# receiver.net
KiCad netlist of a schematic drawn in EAGLE
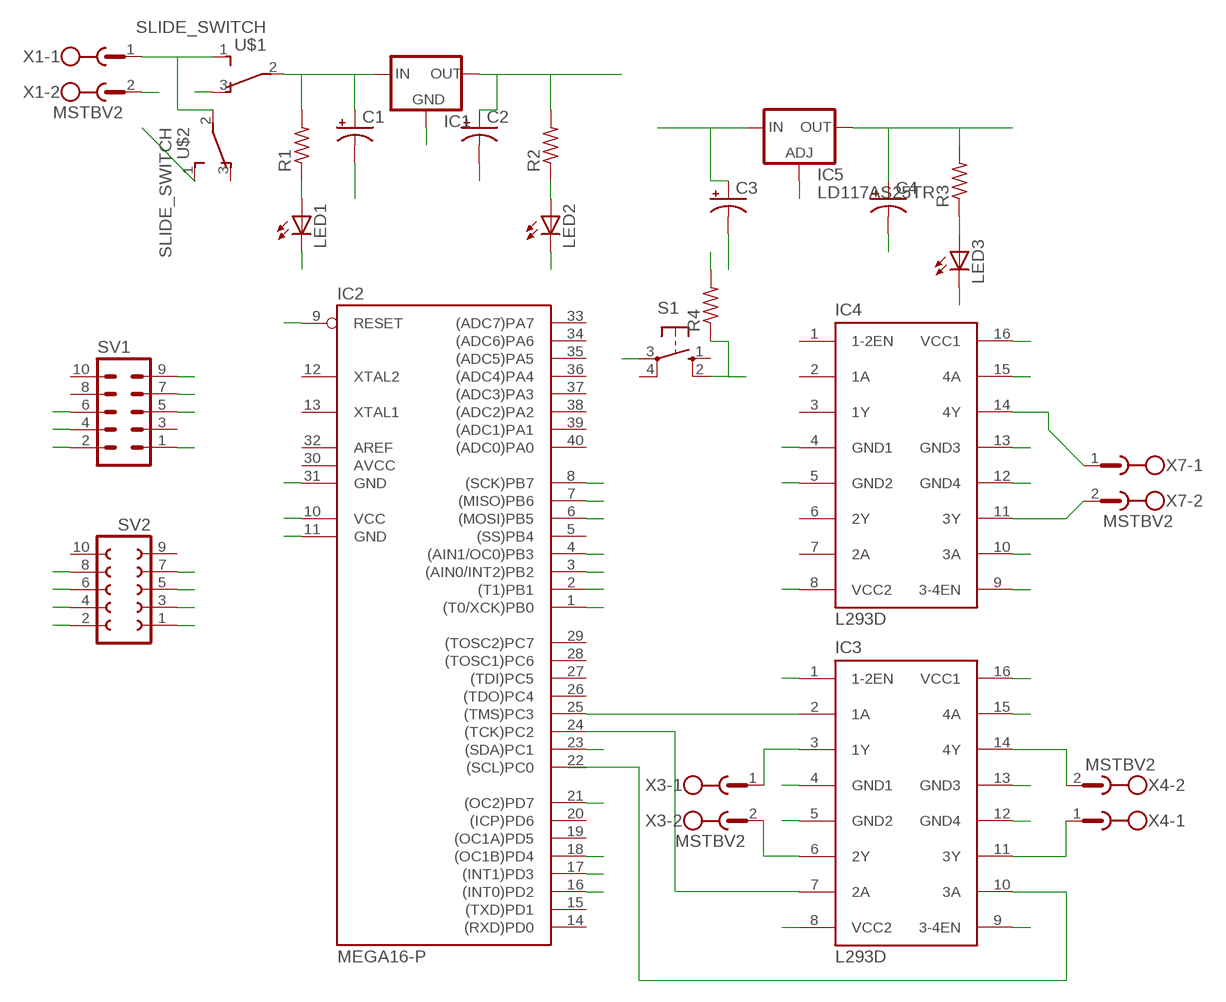
[diagram p0: schematic, sheet 1]

(export (version "E")
  (design (tool "Eeschema 10.0.6"))
  (components
    (comp (ref "C1")
      (value "CPOL-USE2.5-6")
      (footprint "eagle-import:E2,5-6")
      (libsource (lib "eagle-import") (part "CPOL-USE2.5-6"))
    )
    (comp (ref "C2")
      (value "CPOL-USE2.5-6")
      (footprint "eagle-import:E2,5-6")
      (libsource (lib "eagle-import") (part "CPOL-USE2.5-6"))
    )
    (comp (ref "C3")
      (value "CPOL-USE2.5-6")
      (footprint "eagle-import:E2,5-6")
      (libsource (lib "eagle-import") (part "CPOL-USE2.5-6"))
    )
    (comp (ref "C4")
      (value "CPOL-USE2.5-6")
      (footprint "eagle-import:E2,5-6")
      (libsource (lib "eagle-import") (part "CPOL-USE2.5-6"))
    )
    (comp (ref "IC1")
      (value "78XXS")
      (footprint "eagle-import:78XXS")
      (libsource (lib "eagle-import") (part "78XXS"))
    )
    (comp (ref "IC2")
      (value "MEGA16-P")
      (footprint "eagle-import:DIL40")
      (fields (field (name "MPN") "ATMEGA16-16PU"))
      (libsource (lib "eagle-import") (part "MEGA16-P"))
    )
    (comp (ref "IC3")
      (value "L293D")
      (footprint "eagle-import:DIL16")
      (libsource (lib "eagle-import") (part "L293D"))
    )
    (comp (ref "IC4")
      (value "L293D")
      (footprint "eagle-import:DIL16")
      (libsource (lib "eagle-import") (part "L293D"))
    )
    (comp (ref "IC5")
      (value "LD117AS25TR")
      (footprint "eagle-import:SOT223")
      (libsource (lib "eagle-import") (part "LD117A?S25TR"))
    )
    (comp (ref "LED1")
      (value "LED3MM")
      (footprint "eagle-import:LED3MM")
      (libsource (lib "eagle-import") (part "LED3MM"))
    )
    (comp (ref "LED2")
      (value "LED3MM")
      (footprint "eagle-import:LED3MM")
      (libsource (lib "eagle-import") (part "LED3MM"))
    )
    (comp (ref "LED3")
      (value "LED3MM")
      (footprint "eagle-import:LED3MM")
      (libsource (lib "eagle-import") (part "LED3MM"))
    )
    (comp (ref "R1")
      (value "R-US_0207/10")
      (footprint "eagle-import:0207_10")
      (libsource (lib "eagle-import") (part "R-US_0207/10"))
    )
    (comp (ref "R2")
      (value "R-US_0207/10")
      (footprint "eagle-import:0207_10")
      (libsource (lib "eagle-import") (part "R-US_0207/10"))
    )
    (comp (ref "R3")
      (value "R-US_0207/10")
      (footprint "eagle-import:0207_10")
      (libsource (lib "eagle-import") (part "R-US_0207/10"))
    )
    (comp (ref "R4")
      (value "R-US_0207/10")
      (footprint "eagle-import:0207_10")
      (libsource (lib "eagle-import") (part "R-US_0207/10"))
    )
    (comp (ref "S1")
      (value "10-XX")
      (footprint "eagle-import:B3F-10XX")
      (fields (field (name "MPN") "B3F-1000"))
      (libsource (lib "eagle-import") (part "10-XX"))
    )
    (comp (ref "SV1")
      (value "ML10")
      (footprint "eagle-import:ML10")
      (libsource (lib "eagle-import") (part "ML10"))
    )
    (comp (ref "SV2")
      (value "FE05-2")
      (footprint "eagle-import:FE05-2")
      (libsource (lib "eagle-import") (part "FE05-2"))
    )
    (comp (ref "U$1")
      (value "SLIDE_SWITCH")
      (footprint "eagle-import:SPDT")
      (libsource (lib "eagle-import") (part "SLIDE_SWITCH"))
    )
    (comp (ref "U$2")
      (value "SLIDE_SWITCH")
      (footprint "eagle-import:SPDT")
      (libsource (lib "eagle-import") (part "SLIDE_SWITCH"))
    )
    (comp (ref "X1")
      (value "MSTBV2")
      (footprint "eagle-import:MSTBV2")
      (fields (field (name "MPN") "MSTBV 2,5/2-GF-5.08"))
      (libsource (lib "eagle-import") (part "MSTBV2"))
    )
    (comp (ref "X3")
      (value "MSTBV2")
      (footprint "eagle-import:MSTBV2")
      (fields (field (name "MPN") "MSTBV 2,5/2-GF-5.08"))
      (libsource (lib "eagle-import") (part "MSTBV2"))
    )
    (comp (ref "X4")
      (value "MSTBV2")
      (footprint "eagle-import:MSTBV2")
      (fields (field (name "MPN") "MSTBV 2,5/2-GF-5.08"))
      (libsource (lib "eagle-import") (part "MSTBV2"))
    )
    (comp (ref "X7")
      (value "MSTBV2")
      (footprint "eagle-import:MSTBV2")
      (fields (field (name "MPN") "MSTBV 2,5/2-GF-5.08"))
      (libsource (lib "eagle-import") (part "MSTBV2"))
    )
  )
  (nets
    (net (code "1") (name "/16") (class "Default")
      (node (ref "IC2") (pin "16") (pinfunction "(INT0)PD2_16") (pintype "bidirectional"))
      (node (ref "IC4") (pin "15") (pinfunction "4A_15") (pintype "input"))
    )
    (net (code "2") (name "/17") (class "Default")
      (node (ref "IC2") (pin "17") (pinfunction "(INT1)PD3_17") (pintype "bidirectional"))
      (node (ref "IC4") (pin "10") (pinfunction "3A_10") (pintype "input"))
    )
    (net (code "3") (name "/23") (class "Default")
      (node (ref "IC2") (pin "23") (pinfunction "(SDA)PC1_23") (pintype "bidirectional"))
      (node (ref "IC3") (pin "15") (pinfunction "4A_15") (pintype "input"))
    )
    (net (code "4") (name "/AVCC") (class "Default")
      (node (ref "IC2") (pin "30") (pinfunction "AVCC_30") (pintype "power_in"))
    )
    (net (code "5") (name "/CE") (class "Default")
      (node (ref "IC2") (pin "1") (pinfunction "(T0/XCK)PB0_1") (pintype "bidirectional"))
      (node (ref "SV2") (pin "3") (pinfunction "3_3") (pintype "passive"))
    )
    (net (code "6") (name "/CSN") (class "Default")
      (node (ref "IC2") (pin "2") (pinfunction "(T1)PB1_2") (pintype "bidirectional"))
      (node (ref "SV2") (pin "4") (pinfunction "4_4") (pintype "passive"))
    )
    (net (code "7") (name "/EN12") (class "Default")
      (node (ref "IC2") (pin "4") (pinfunction "(AIN1/OC0)PB3_4") (pintype "bidirectional"))
      (node (ref "IC3") (pin "1") (pinfunction "1-2EN_1") (pintype "input"))
    )
    (net (code "8") (name "/EN34") (class "Default")
      (node (ref "IC2") (pin "21") (pinfunction "(OC2)PD7_21") (pintype "bidirectional"))
      (node (ref "IC3") (pin "9") (pinfunction "3-4EN_9") (pintype "input"))
    )
    (net (code "9") (name "/GND") (class "Default")
      (node (ref "C1") (pin "-") (pinfunction "-_-") (pintype "passive"))
      (node (ref "C2") (pin "-") (pinfunction "-_-") (pintype "passive"))
      (node (ref "C3") (pin "-") (pinfunction "-_-") (pintype "passive"))
      (node (ref "C4") (pin "-") (pinfunction "-_-") (pintype "passive"))
      (node (ref "IC1") (pin "GND") (pinfunction "GND_GND") (pintype "input"))
      (node (ref "IC2") (pin "11") (pinfunction "GND_11") (pintype "power_in"))
      (node (ref "IC2") (pin "31") (pinfunction "GND_31") (pintype "power_in"))
      (node (ref "IC3") (pin "12") (pinfunction "GND4_12") (pintype "power_in"))
      (node (ref "IC3") (pin "13") (pinfunction "GND3_13") (pintype "power_in"))
      (node (ref "IC3") (pin "4") (pinfunction "GND1_4") (pintype "power_in"))
      (node (ref "IC3") (pin "5") (pinfunction "GND2_5") (pintype "power_in"))
      (node (ref "IC4") (pin "12") (pinfunction "GND4_12") (pintype "power_in"))
      (node (ref "IC4") (pin "13") (pinfunction "GND3_13") (pintype "power_in"))
      (node (ref "IC4") (pin "4") (pinfunction "GND1_4") (pintype "power_in"))
      (node (ref "IC4") (pin "5") (pinfunction "GND2_5") (pintype "power_in"))
      (node (ref "IC5") (pin "1") (pinfunction "ADJ_1") (pintype "input"))
      (node (ref "LED1") (pin "K") (pinfunction "C_K") (pintype "passive"))
      (node (ref "LED2") (pin "K") (pinfunction "C_K") (pintype "passive"))
      (node (ref "LED3") (pin "K") (pinfunction "C_K") (pintype "passive"))
      (node (ref "S1") (pin "3") (pinfunction "P_3") (pintype "passive"))
      (node (ref "SV1") (pin "4") (pinfunction "4_4") (pintype "passive"))
      (node (ref "SV1") (pin "6") (pinfunction "6_6") (pintype "passive"))
      (node (ref "SV2") (pin "1") (pinfunction "1_1") (pintype "passive"))
      (node (ref "U$1") (pin "3") (pinfunction "NC_3") (pintype "passive"))
      (node (ref "X1") (pin "2") (pinfunction "1_2") (pintype "passive"))
    )
    (net (code "10") (name "/IRQ") (class "Default")
      (node (ref "IC2") (pin "3") (pinfunction "(AIN0/INT2)PB2_3") (pintype "bidirectional"))
      (node (ref "SV2") (pin "8") (pinfunction "8_8") (pintype "passive"))
    )
    (net (code "11") (name "/MISO") (class "Default")
      (node (ref "IC2") (pin "7") (pinfunction "(MISO)PB6_7") (pintype "bidirectional"))
      (node (ref "SV1") (pin "9") (pinfunction "9_9") (pintype "passive"))
      (node (ref "SV2") (pin "7") (pinfunction "7_7") (pintype "passive"))
    )
    (net (code "12") (name "/MOSI") (class "Default")
      (node (ref "IC2") (pin "6") (pinfunction "(MOSI)PB5_6") (pintype "bidirectional"))
      (node (ref "SV1") (pin "1") (pinfunction "1_1") (pintype "passive"))
      (node (ref "SV2") (pin "6") (pinfunction "6_6") (pintype "passive"))
    )
    (net (code "13") (name "/OC1B") (class "Default")
      (node (ref "IC2") (pin "18") (pinfunction "(OC1B)PD4_18") (pintype "bidirectional"))
      (node (ref "IC4") (pin "9") (pinfunction "3-4EN_9") (pintype "input"))
    )
    (net (code "14") (name "/RST") (class "Default")
      (node (ref "IC2") (pin "9") (pinfunction "RESET_9") (pintype "input"))
      (node (ref "R4") (pin "1") (pinfunction "1_1") (pintype "passive"))
      (node (ref "S1") (pin "2") (pinfunction "S1_2") (pintype "passive"))
      (node (ref "SV1") (pin "5") (pinfunction "5_5") (pintype "passive"))
    )
    (net (code "15") (name "/SCK") (class "Default")
      (node (ref "IC2") (pin "8") (pinfunction "(SCK)PB7_8") (pintype "bidirectional"))
      (node (ref "SV1") (pin "7") (pinfunction "7_7") (pintype "passive"))
      (node (ref "SV2") (pin "5") (pinfunction "5_5") (pintype "passive"))
    )
    (net (code "16") (name "/VCC") (class "Default")
      (node (ref "C2") (pin "+") (pinfunction "+_+") (pintype "passive"))
      (node (ref "C3") (pin "+") (pinfunction "+_+") (pintype "passive"))
      (node (ref "IC1") (pin "OUT") (pinfunction "OUT_OUT") (pintype "passive"))
      (node (ref "IC2") (pin "10") (pinfunction "VCC_10") (pintype "power_in"))
      (node (ref "IC3") (pin "16") (pinfunction "VCC1_16") (pintype "power_in"))
      (node (ref "IC4") (pin "16") (pinfunction "VCC1_16") (pintype "power_in"))
      (node (ref "IC5") (pin "3") (pinfunction "IN_3") (pintype "input"))
      (node (ref "R2") (pin "2") (pinfunction "2_2") (pintype "passive"))
      (node (ref "R4") (pin "2") (pinfunction "2_2") (pintype "passive"))
      (node (ref "SV1") (pin "2") (pinfunction "2_2") (pintype "passive"))
    )
    (net (code "17") (name "/VCC3.3") (class "Default")
      (node (ref "C4") (pin "+") (pinfunction "+_+") (pintype "passive"))
      (node (ref "IC5") (pin "4") (pinfunction "OUT_4") (pintype "passive"))
      (node (ref "R3") (pin "2") (pinfunction "2_2") (pintype "passive"))
      (node (ref "SV2") (pin "2") (pinfunction "2_2") (pintype "passive"))
    )
    (net (code "18") (name "/VCC12") (class "Default")
      (node (ref "IC3") (pin "8") (pinfunction "VCC2_8") (pintype "power_in"))
      (node (ref "IC4") (pin "8") (pinfunction "VCC2_8") (pintype "power_in"))
      (node (ref "U$2") (pin "1") (pinfunction "NO_1") (pintype "passive"))
    )
    (net (code "19") (name "Net-(IC2-(SCL)PC0)") (class "Default")
      (node (ref "IC2") (pin "22") (pinfunction "(SCL)PC0_22") (pintype "bidirectional"))
      (node (ref "IC3") (pin "10") (pinfunction "3A_10") (pintype "input"))
    )
    (net (code "20") (name "Net-(IC2-(TCK)PC2)") (class "Default")
      (node (ref "IC2") (pin "24") (pinfunction "(TCK)PC2_24") (pintype "bidirectional"))
      (node (ref "IC3") (pin "7") (pinfunction "2A_7") (pintype "input"))
    )
    (net (code "21") (name "Net-(IC2-(TMS)PC3)") (class "Default")
      (node (ref "IC2") (pin "25") (pinfunction "(TMS)PC3_25") (pintype "bidirectional"))
      (node (ref "IC3") (pin "2") (pinfunction "1A_2") (pintype "input"))
    )
    (net (code "22") (name "Net-(IC3-1Y)") (class "Default")
      (node (ref "IC3") (pin "3") (pinfunction "1Y_3") (pintype "output"))
      (node (ref "X3") (pin "1") (pinfunction "1_1") (pintype "passive"))
    )
    (net (code "23") (name "Net-(IC3-2Y)") (class "Default")
      (node (ref "IC3") (pin "6") (pinfunction "2Y_6") (pintype "output"))
      (node (ref "X3") (pin "2") (pinfunction "1_2") (pintype "passive"))
    )
    (net (code "24") (name "Net-(IC3-3Y)") (class "Default")
      (node (ref "IC3") (pin "11") (pinfunction "3Y_11") (pintype "output"))
      (node (ref "X4") (pin "1") (pinfunction "1_1") (pintype "passive"))
    )
    (net (code "25") (name "Net-(IC3-4Y)") (class "Default")
      (node (ref "IC3") (pin "14") (pinfunction "4Y_14") (pintype "output"))
      (node (ref "X4") (pin "2") (pinfunction "1_2") (pintype "passive"))
    )
    (net (code "26") (name "Net-(IC4-3Y)") (class "Default")
      (node (ref "IC4") (pin "11") (pinfunction "3Y_11") (pintype "output"))
      (node (ref "X7") (pin "2") (pinfunction "1_2") (pintype "passive"))
    )
    (net (code "27") (name "Net-(IC4-4Y)") (class "Default")
      (node (ref "IC4") (pin "14") (pinfunction "4Y_14") (pintype "output"))
      (node (ref "X7") (pin "1") (pinfunction "1_1") (pintype "passive"))
    )
    (net (code "28") (name "Net-(LED1-PadA)") (class "Default")
      (node (ref "LED1") (pin "A") (pinfunction "A_A") (pintype "passive"))
      (node (ref "R1") (pin "1") (pinfunction "1_1") (pintype "passive"))
    )
    (net (code "29") (name "Net-(LED2-PadA)") (class "Default")
      (node (ref "LED2") (pin "A") (pinfunction "A_A") (pintype "passive"))
      (node (ref "R2") (pin "1") (pinfunction "1_1") (pintype "passive"))
    )
    (net (code "30") (name "Net-(LED3-PadA)") (class "Default")
      (node (ref "LED3") (pin "A") (pinfunction "A_A") (pintype "passive"))
      (node (ref "R3") (pin "1") (pinfunction "1_1") (pintype "passive"))
    )
    (net (code "31") (name "Net-(U$1-NO)") (class "Default")
      (node (ref "U$1") (pin "1") (pinfunction "NO_1") (pintype "passive"))
      (node (ref "U$2") (pin "2") (pinfunction "P_2") (pintype "passive"))
      (node (ref "X1") (pin "1") (pinfunction "1_1") (pintype "passive"))
    )
    (net (code "32") (name "Net-(U$1-P)") (class "Default")
      (node (ref "C1") (pin "+") (pinfunction "+_+") (pintype "passive"))
      (node (ref "IC1") (pin "IN") (pinfunction "IN_IN") (pintype "input"))
      (node (ref "R1") (pin "2") (pinfunction "2_2") (pintype "passive"))
      (node (ref "U$1") (pin "2") (pinfunction "P_2") (pintype "passive"))
    )
    (net (code "33") (name "unconnected-(IC2-(ADC0)PA0-Pad40)") (class "Default")
      (node (ref "IC2") (pin "40") (pinfunction "(ADC0)PA0_40") (pintype "bidirectional"))
    )
    (net (code "34") (name "unconnected-(IC2-(ADC1)PA1-Pad39)") (class "Default")
      (node (ref "IC2") (pin "39") (pinfunction "(ADC1)PA1_39") (pintype "bidirectional"))
    )
    (net (code "35") (name "unconnected-(IC2-(ADC2)PA2-Pad38)") (class "Default")
      (node (ref "IC2") (pin "38") (pinfunction "(ADC2)PA2_38") (pintype "bidirectional"))
    )
    (net (code "36") (name "unconnected-(IC2-(ADC3)PA3-Pad37)") (class "Default")
      (node (ref "IC2") (pin "37") (pinfunction "(ADC3)PA3_37") (pintype "bidirectional"))
    )
    (net (code "37") (name "unconnected-(IC2-(ADC4)PA4-Pad36)") (class "Default")
      (node (ref "IC2") (pin "36") (pinfunction "(ADC4)PA4_36") (pintype "bidirectional"))
    )
    (net (code "38") (name "unconnected-(IC2-(ADC5)PA5-Pad35)") (class "Default")
      (node (ref "IC2") (pin "35") (pinfunction "(ADC5)PA5_35") (pintype "bidirectional"))
    )
    (net (code "39") (name "unconnected-(IC2-(ADC6)PA6-Pad34)") (class "Default")
      (node (ref "IC2") (pin "34") (pinfunction "(ADC6)PA6_34") (pintype "bidirectional"))
    )
    (net (code "40") (name "unconnected-(IC2-(ADC7)PA7-Pad33)") (class "Default")
      (node (ref "IC2") (pin "33") (pinfunction "(ADC7)PA7_33") (pintype "bidirectional"))
    )
    (net (code "41") (name "unconnected-(IC2-(ICP)PD6-Pad20)") (class "Default")
      (node (ref "IC2") (pin "20") (pinfunction "(ICP)PD6_20") (pintype "bidirectional"))
    )
    (net (code "42") (name "unconnected-(IC2-(OC1A)PD5-Pad19)") (class "Default")
      (node (ref "IC2") (pin "19") (pinfunction "(OC1A)PD5_19") (pintype "bidirectional"))
    )
    (net (code "43") (name "unconnected-(IC2-(RXD)PD0-Pad14)") (class "Default")
      (node (ref "IC2") (pin "14") (pinfunction "(RXD)PD0_14") (pintype "bidirectional"))
    )
    (net (code "44") (name "unconnected-(IC2-(SS)PB4-Pad5)") (class "Default")
      (node (ref "IC2") (pin "5") (pinfunction "(SS)PB4_5") (pintype "bidirectional"))
    )
    (net (code "45") (name "unconnected-(IC2-(TDI)PC5-Pad27)") (class "Default")
      (node (ref "IC2") (pin "27") (pinfunction "(TDI)PC5_27") (pintype "bidirectional"))
    )
    (net (code "46") (name "unconnected-(IC2-(TDO)PC4-Pad26)") (class "Default")
      (node (ref "IC2") (pin "26") (pinfunction "(TDO)PC4_26") (pintype "bidirectional"))
    )
    (net (code "47") (name "unconnected-(IC2-(TOSC1)PC6-Pad28)") (class "Default")
      (node (ref "IC2") (pin "28") (pinfunction "(TOSC1)PC6_28") (pintype "bidirectional"))
    )
    (net (code "48") (name "unconnected-(IC2-(TOSC2)PC7-Pad29)") (class "Default")
      (node (ref "IC2") (pin "29") (pinfunction "(TOSC2)PC7_29") (pintype "bidirectional"))
    )
    (net (code "49") (name "unconnected-(IC2-(TXD)PD1-Pad15)") (class "Default")
      (node (ref "IC2") (pin "15") (pinfunction "(TXD)PD1_15") (pintype "bidirectional"))
    )
    (net (code "50") (name "unconnected-(IC2-AREF-Pad32)") (class "Default")
      (node (ref "IC2") (pin "32") (pinfunction "AREF_32") (pintype "passive"))
    )
    (net (code "51") (name "unconnected-(IC2-XTAL1-Pad13)") (class "Default")
      (node (ref "IC2") (pin "13") (pinfunction "XTAL1_13") (pintype "bidirectional"))
    )
    (net (code "52") (name "unconnected-(IC2-XTAL2-Pad12)") (class "Default")
      (node (ref "IC2") (pin "12") (pinfunction "XTAL2_12") (pintype "bidirectional"))
    )
    (net (code "53") (name "unconnected-(IC4-1-2EN-Pad1)") (class "Default")
      (node (ref "IC4") (pin "1") (pinfunction "1-2EN_1") (pintype "input"))
    )
    (net (code "54") (name "unconnected-(IC4-1A-Pad2)") (class "Default")
      (node (ref "IC4") (pin "2") (pinfunction "1A_2") (pintype "input"))
    )
    (net (code "55") (name "unconnected-(IC4-1Y-Pad3)") (class "Default")
      (node (ref "IC4") (pin "3") (pinfunction "1Y_3") (pintype "output"))
    )
    (net (code "56") (name "unconnected-(IC4-2A-Pad7)") (class "Default")
      (node (ref "IC4") (pin "7") (pinfunction "2A_7") (pintype "input"))
    )
    (net (code "57") (name "unconnected-(IC4-2Y-Pad6)") (class "Default")
      (node (ref "IC4") (pin "6") (pinfunction "2Y_6") (pintype "output"))
    )
    (net (code "58") (name "unconnected-(S1-P1-Pad4)") (class "Default")
      (node (ref "S1") (pin "4") (pinfunction "P1_4") (pintype "passive"))
    )
    (net (code "59") (name "unconnected-(S1-S-Pad1)") (class "Default")
      (node (ref "S1") (pin "1") (pinfunction "S_1") (pintype "passive"))
    )
    (net (code "60") (name "unconnected-(SV1-Pad3)") (class "Default")
      (node (ref "SV1") (pin "3") (pinfunction "3_3") (pintype "passive"))
    )
    (net (code "61") (name "unconnected-(SV1-Pad8)") (class "Default")
      (node (ref "SV1") (pin "8") (pinfunction "8_8") (pintype "passive"))
    )
    (net (code "62") (name "unconnected-(SV1-Pad10)") (class "Default")
      (node (ref "SV1") (pin "10") (pinfunction "10_10") (pintype "passive"))
    )
    (net (code "63") (name "unconnected-(SV2-Pad9)") (class "Default")
      (node (ref "SV2") (pin "9") (pinfunction "9_9") (pintype "passive"))
    )
    (net (code "64") (name "unconnected-(SV2-Pad10)") (class "Default")
      (node (ref "SV2") (pin "10") (pinfunction "10_10") (pintype "passive"))
    )
    (net (code "65") (name "unconnected-(U$2-NC-Pad3)") (class "Default")
      (node (ref "U$2") (pin "3") (pinfunction "NC_3") (pintype "passive"))
    )
  )
)
